# 154N_NAU7802.net
KiCad netlist of a schematic drawn in EAGLE
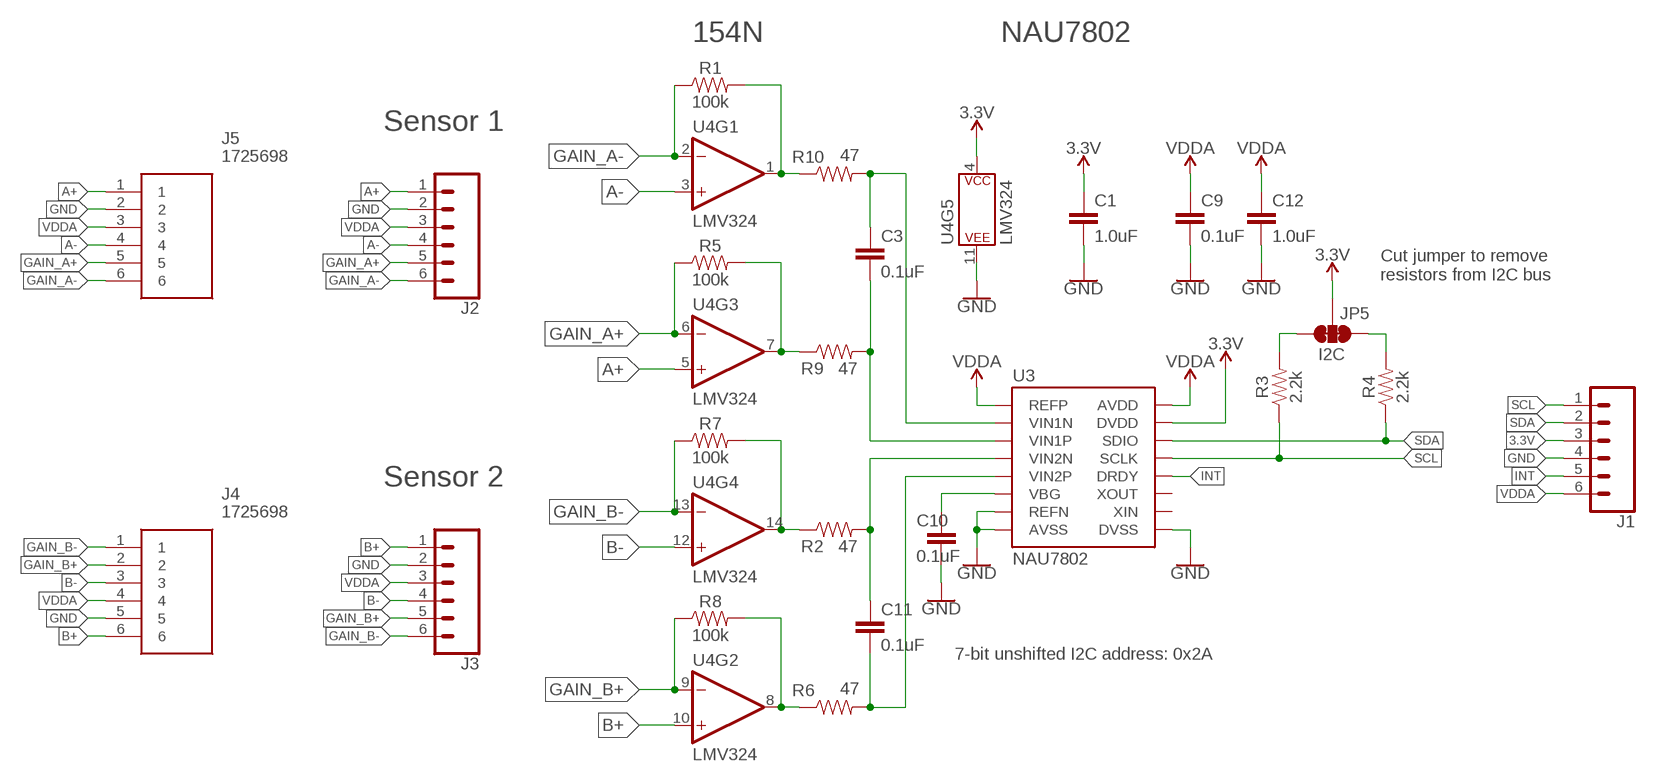
[diagram p0: schematic, sheet 1]

(export (version "E")
  (design (tool "Eeschema 10.0.6"))
  (components
    (comp (ref "C1")
      (value "1.0uF")
      (footprint "eagle-import:0603")
      (libsource (lib "eagle-import") (part "1.0UF-0603-16V-10%"))
    )
    (comp (ref "C3")
      (value "0.1uF")
      (footprint "eagle-import:0603")
      (libsource (lib "eagle-import") (part "0.1UF-0603-25V-(+80/-20%)"))
    )
    (comp (ref "C9")
      (value "0.1uF")
      (footprint "eagle-import:0603")
      (libsource (lib "eagle-import") (part "0.1UF-0603-25V-(+80/-20%)"))
    )
    (comp (ref "C10")
      (value "0.1uF")
      (footprint "eagle-import:0603")
      (libsource (lib "eagle-import") (part "0.1UF-0603-25V-(+80/-20%)"))
    )
    (comp (ref "C11")
      (value "0.1uF")
      (footprint "eagle-import:0603")
      (libsource (lib "eagle-import") (part "0.1UF-0603-25V-(+80/-20%)"))
    )
    (comp (ref "C12")
      (value "1.0uF")
      (footprint "eagle-import:0603")
      (libsource (lib "eagle-import") (part "1.0UF-0603-16V-10%"))
    )
    (comp (ref "J1")
      (value "CONN_06SILK_FEMALE_PTH")
      (footprint "eagle-import:1X06")
      (libsource (lib "eagle-import") (part "CONN_06SILK_FEMALE_PTH"))
    )
    (comp (ref "J2")
      (value "CONN_06SILK_FEMALE_PTH")
      (footprint "eagle-import:1X06")
      (libsource (lib "eagle-import") (part "CONN_06SILK_FEMALE_PTH"))
    )
    (comp (ref "J3")
      (value "CONN_06SILK_FEMALE_PTH")
      (footprint "eagle-import:1X06")
      (libsource (lib "eagle-import") (part "CONN_06SILK_FEMALE_PTH"))
    )
    (comp (ref "J4")
      (value "1725698")
      (footprint "eagle-import:SHDR6W90P0X254_1X6_1570X620X85")
      (fields (field (name "RS_PART_NUMBER") "3909045"))
      (libsource (lib "eagle-import") (part "1725698"))
    )
    (comp (ref "J5")
      (value "1725698")
      (footprint "eagle-import:SHDR6W90P0X254_1X6_1570X620X85")
      (fields (field (name "RS_PART_NUMBER") "3909045"))
      (libsource (lib "eagle-import") (part "1725698"))
    )
    (comp (ref "JP5")
      (value "I2C")
      (footprint "eagle-import:SMT-JUMPER_3_2-NC_TRACE_SILK")
      (libsource (lib "eagle-import") (part "JUMPER-SMT_3_2-NC_TRACE_SILK"))
    )
    (comp (ref "R1")
      (value "100k")
      (footprint "eagle-import:0603")
      (libsource (lib "eagle-import") (part "100KOHM-0603-1/10W-1%"))
    )
    (comp (ref "R2")
      (value "47")
      (footprint "eagle-import:0603")
      (libsource (lib "eagle-import") (part "47OHM-0603-1/10W-1%"))
    )
    (comp (ref "R3")
      (value "2.2k")
      (footprint "eagle-import:0603")
      (libsource (lib "eagle-import") (part "2.2KOHM-0603-1/10W-1%"))
    )
    (comp (ref "R4")
      (value "2.2k")
      (footprint "eagle-import:0603")
      (libsource (lib "eagle-import") (part "2.2KOHM-0603-1/10W-1%"))
    )
    (comp (ref "R5")
      (value "100k")
      (footprint "eagle-import:0603")
      (libsource (lib "eagle-import") (part "100KOHM-0603-1/10W-1%"))
    )
    (comp (ref "R6")
      (value "47")
      (footprint "eagle-import:0603")
      (libsource (lib "eagle-import") (part "47OHM-0603-1/10W-1%"))
    )
    (comp (ref "R7")
      (value "100k")
      (footprint "eagle-import:0603")
      (libsource (lib "eagle-import") (part "100KOHM-0603-1/10W-1%"))
    )
    (comp (ref "R8")
      (value "100k")
      (footprint "eagle-import:0603")
      (libsource (lib "eagle-import") (part "100KOHM-0603-1/10W-1%"))
    )
    (comp (ref "R9")
      (value "47")
      (footprint "eagle-import:0603")
      (libsource (lib "eagle-import") (part "47OHM-0603-1/10W-1%"))
    )
    (comp (ref "R10")
      (value "47")
      (footprint "eagle-import:0603")
      (libsource (lib "eagle-import") (part "47OHM-0603-1/10W-1%"))
    )
    (comp (ref "U3")
      (value "NAU7802")
      (footprint "eagle-import:SPARKFUN-IC-CONVERSION_SO16")
      (libsource (lib "eagle-import") (part "SPARKFUN-IC-CONVERSION_NAU7802SOIC"))
    )
    (comp (ref "U4")
      (value "LMV324")
      (footprint "eagle-import:SPARKFUN-IC-AMPLIFIERS_SO14")
      (libsource (lib "eagle-import") (part "SPARKFUN-IC-AMPLIFIERS_LMV324"))
    )
  )
  (nets
    (net (code "1") (name "3.3V") (class "Default")
      (node (ref "C1") (pin "1") (pinfunction "1_1") (pintype "passive"))
      (node (ref "J1") (pin "3") (pinfunction "3_3") (pintype "passive"))
      (node (ref "JP5") (pin "2") (pinfunction "2_2") (pintype "passive"))
      (node (ref "U3") (pin "15") (pinfunction "DVDD_15") (pintype "bidirectional"))
      (node (ref "U4") (pin "4") (pinfunction "P$V+_4") (pintype "bidirectional"))
    )
    (net (code "2") (name "A+") (class "Default")
      (node (ref "J2") (pin "1") (pinfunction "1_1") (pintype "passive"))
      (node (ref "J5") (pin "1") (pinfunction "1_1") (pintype "bidirectional"))
      (node (ref "U4") (pin "5") (pinfunction "+IN_5") (pintype "input"))
    )
    (net (code "3") (name "A-") (class "Default")
      (node (ref "J2") (pin "4") (pinfunction "4_4") (pintype "passive"))
      (node (ref "J5") (pin "4") (pinfunction "4_4") (pintype "bidirectional"))
      (node (ref "U4") (pin "3") (pinfunction "+IN_3") (pintype "input"))
    )
    (net (code "4") (name "B+") (class "Default")
      (node (ref "J3") (pin "1") (pinfunction "1_1") (pintype "passive"))
      (node (ref "J4") (pin "6") (pinfunction "6_6") (pintype "bidirectional"))
      (node (ref "U4") (pin "10") (pinfunction "+IN_10") (pintype "input"))
    )
    (net (code "5") (name "B-") (class "Default")
      (node (ref "J3") (pin "4") (pinfunction "4_4") (pintype "passive"))
      (node (ref "J4") (pin "3") (pinfunction "3_3") (pintype "bidirectional"))
      (node (ref "U4") (pin "12") (pinfunction "+IN_12") (pintype "input"))
    )
    (net (code "6") (name "GAIN_A+") (class "Default")
      (node (ref "J2") (pin "5") (pinfunction "5_5") (pintype "passive"))
      (node (ref "J5") (pin "5") (pinfunction "5_5") (pintype "bidirectional"))
      (node (ref "R5") (pin "1") (pinfunction "1_1") (pintype "passive"))
      (node (ref "U4") (pin "6") (pinfunction "-IN_6") (pintype "input"))
    )
    (net (code "7") (name "GAIN_A-") (class "Default")
      (node (ref "J2") (pin "6") (pinfunction "6_6") (pintype "passive"))
      (node (ref "J5") (pin "6") (pinfunction "6_6") (pintype "bidirectional"))
      (node (ref "R1") (pin "1") (pinfunction "1_1") (pintype "passive"))
      (node (ref "U4") (pin "2") (pinfunction "-IN_2") (pintype "input"))
    )
    (net (code "8") (name "GAIN_B+") (class "Default")
      (node (ref "J3") (pin "5") (pinfunction "5_5") (pintype "passive"))
      (node (ref "J4") (pin "2") (pinfunction "2_2") (pintype "bidirectional"))
      (node (ref "R8") (pin "1") (pinfunction "1_1") (pintype "passive"))
      (node (ref "U4") (pin "9") (pinfunction "-IN_9") (pintype "input"))
    )
    (net (code "9") (name "GAIN_B-") (class "Default")
      (node (ref "J3") (pin "6") (pinfunction "6_6") (pintype "passive"))
      (node (ref "J4") (pin "1") (pinfunction "1_1") (pintype "bidirectional"))
      (node (ref "R7") (pin "1") (pinfunction "1_1") (pintype "passive"))
      (node (ref "U4") (pin "13") (pinfunction "-IN_13") (pintype "input"))
    )
    (net (code "10") (name "GND") (class "Default")
      (node (ref "C1") (pin "2") (pinfunction "2_2") (pintype "passive"))
      (node (ref "C10") (pin "2") (pinfunction "2_2") (pintype "passive"))
      (node (ref "C12") (pin "2") (pinfunction "2_2") (pintype "passive"))
      (node (ref "C9") (pin "2") (pinfunction "2_2") (pintype "passive"))
      (node (ref "J1") (pin "4") (pinfunction "4_4") (pintype "passive"))
      (node (ref "J2") (pin "2") (pinfunction "2_2") (pintype "passive"))
      (node (ref "J3") (pin "2") (pinfunction "2_2") (pintype "passive"))
      (node (ref "J4") (pin "5") (pinfunction "5_5") (pintype "bidirectional"))
      (node (ref "J5") (pin "2") (pinfunction "2_2") (pintype "bidirectional"))
      (node (ref "U3") (pin "7") (pinfunction "REFN_7") (pintype "bidirectional"))
      (node (ref "U3") (pin "8") (pinfunction "AVSS_8") (pintype "bidirectional"))
      (node (ref "U3") (pin "9") (pinfunction "DVSS_9") (pintype "bidirectional"))
      (node (ref "U4") (pin "11") (pinfunction "P$V-_11") (pintype "bidirectional"))
    )
    (net (code "11") (name "INT") (class "Default")
      (node (ref "J1") (pin "5") (pinfunction "5_5") (pintype "passive"))
      (node (ref "U3") (pin "12") (pinfunction "DRDY_12") (pintype "bidirectional"))
    )
    (net (code "12") (name "Net-(JP5-Pad1)") (class "Default")
      (node (ref "JP5") (pin "1") (pinfunction "1_1") (pintype "passive"))
      (node (ref "R4") (pin "2") (pinfunction "2_2") (pintype "passive"))
    )
    (net (code "13") (name "Net-(JP5-Pad3)") (class "Default")
      (node (ref "JP5") (pin "3") (pinfunction "3_3") (pintype "passive"))
      (node (ref "R3") (pin "2") (pinfunction "2_2") (pintype "passive"))
    )
    (net (code "14") (name "Net-(U3-VBG)") (class "Default")
      (node (ref "C10") (pin "1") (pinfunction "1_1") (pintype "passive"))
      (node (ref "U3") (pin "6") (pinfunction "VBG_6") (pintype "bidirectional"))
    )
    (net (code "15") (name "Net-(U3-VIN1N)") (class "Default")
      (node (ref "C3") (pin "1") (pinfunction "1_1") (pintype "passive"))
      (node (ref "R10") (pin "2") (pinfunction "2_2") (pintype "passive"))
      (node (ref "U3") (pin "2") (pinfunction "VIN1N_2") (pintype "bidirectional"))
    )
    (net (code "16") (name "Net-(U3-VIN1P)") (class "Default")
      (node (ref "C3") (pin "2") (pinfunction "2_2") (pintype "passive"))
      (node (ref "R9") (pin "2") (pinfunction "2_2") (pintype "passive"))
      (node (ref "U3") (pin "3") (pinfunction "VIN1P_3") (pintype "bidirectional"))
    )
    (net (code "17") (name "Net-(U3-VIN2N)") (class "Default")
      (node (ref "C11") (pin "1") (pinfunction "1_1") (pintype "passive"))
      (node (ref "R2") (pin "2") (pinfunction "2_2") (pintype "passive"))
      (node (ref "U3") (pin "4") (pinfunction "VIN2N_4") (pintype "bidirectional"))
    )
    (net (code "18") (name "Net-(U3-VIN2P)") (class "Default")
      (node (ref "C11") (pin "2") (pinfunction "2_2") (pintype "passive"))
      (node (ref "R6") (pin "2") (pinfunction "2_2") (pintype "passive"))
      (node (ref "U3") (pin "5") (pinfunction "VIN2P_5") (pintype "bidirectional"))
    )
    (net (code "19") (name "Net-(U4A-OUT)") (class "Default")
      (node (ref "R1") (pin "2") (pinfunction "2_2") (pintype "passive"))
      (node (ref "R10") (pin "1") (pinfunction "1_1") (pintype "passive"))
      (node (ref "U4") (pin "1") (pinfunction "OUT_1") (pintype "output"))
    )
    (net (code "20") (name "Net-(U4B-OUT)") (class "Default")
      (node (ref "R6") (pin "1") (pinfunction "1_1") (pintype "passive"))
      (node (ref "R8") (pin "2") (pinfunction "2_2") (pintype "passive"))
      (node (ref "U4") (pin "8") (pinfunction "OUT_8") (pintype "output"))
    )
    (net (code "21") (name "Net-(U4C-OUT)") (class "Default")
      (node (ref "R5") (pin "2") (pinfunction "2_2") (pintype "passive"))
      (node (ref "R9") (pin "1") (pinfunction "1_1") (pintype "passive"))
      (node (ref "U4") (pin "7") (pinfunction "OUT_7") (pintype "output"))
    )
    (net (code "22") (name "Net-(U4D-OUT)") (class "Default")
      (node (ref "R2") (pin "1") (pinfunction "1_1") (pintype "passive"))
      (node (ref "R7") (pin "2") (pinfunction "2_2") (pintype "passive"))
      (node (ref "U4") (pin "14") (pinfunction "OUT_14") (pintype "output"))
    )
    (net (code "23") (name "SCL") (class "Default")
      (node (ref "J1") (pin "1") (pinfunction "1_1") (pintype "passive"))
      (node (ref "R3") (pin "1") (pinfunction "1_1") (pintype "passive"))
      (node (ref "U3") (pin "13") (pinfunction "SCLK_13") (pintype "bidirectional"))
    )
    (net (code "24") (name "SDA") (class "Default")
      (node (ref "J1") (pin "2") (pinfunction "2_2") (pintype "passive"))
      (node (ref "R4") (pin "1") (pinfunction "1_1") (pintype "passive"))
      (node (ref "U3") (pin "14") (pinfunction "SDIO_14") (pintype "bidirectional"))
    )
    (net (code "25") (name "VDDA") (class "Default")
      (node (ref "C12") (pin "1") (pinfunction "1_1") (pintype "passive"))
      (node (ref "C9") (pin "1") (pinfunction "1_1") (pintype "passive"))
      (node (ref "J1") (pin "6") (pinfunction "6_6") (pintype "passive"))
      (node (ref "J2") (pin "3") (pinfunction "3_3") (pintype "passive"))
      (node (ref "J3") (pin "3") (pinfunction "3_3") (pintype "passive"))
      (node (ref "J4") (pin "4") (pinfunction "4_4") (pintype "bidirectional"))
      (node (ref "J5") (pin "3") (pinfunction "3_3") (pintype "bidirectional"))
      (node (ref "U3") (pin "1") (pinfunction "REFP_1") (pintype "bidirectional"))
      (node (ref "U3") (pin "16") (pinfunction "AVDD_16") (pintype "bidirectional"))
    )
    (net (code "26") (name "unconnected-(U3-XIN-Pad10)") (class "Default")
      (node (ref "U3") (pin "10") (pinfunction "XIN_10") (pintype "bidirectional"))
    )
    (net (code "27") (name "unconnected-(U3-XOUT-Pad11)") (class "Default")
      (node (ref "U3") (pin "11") (pinfunction "XOUT_11") (pintype "bidirectional"))
    )
  )
)
